# esp8266-dev2.net
KiCad netlist of a schematic drawn in EAGLE
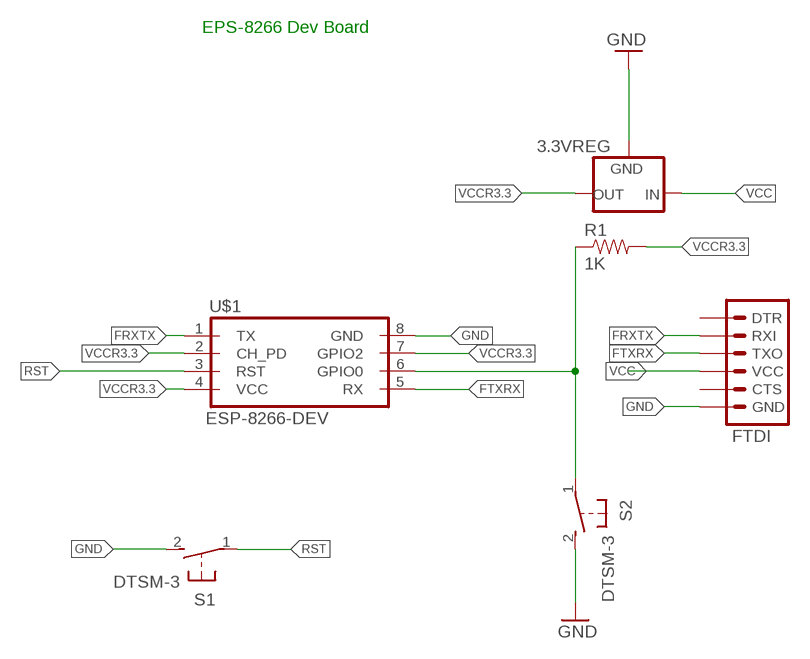
[diagram p0: schematic, sheet 1]

(export (version "E")
  (design (tool "Eeschema 10.0.6"))
  (components
    (comp (ref "3.3VREG")
      (value "LM1117V")
      (footprint "eagle-import:78XXS")
      (libsource (lib "eagle-import") (part "LM1117V"))
    )
    (comp (ref "FTDI")
      (value "ARDUINO_SERIAL_PROGRAMPTH")
      (footprint "eagle-import:1X06")
      (libsource (lib "eagle-import") (part "ARDUINO_SERIAL_PROGRAMPTH"))
    )
    (comp (ref "R1")
      (value "1K")
      (footprint "eagle-import:AXIAL-0.3EZ")
      (fields (field (name "MF") "FARNELL") (field (name "MPN") "MCF 0.25W 1K"))
      (libsource (lib "eagle-import") (part "1KOHM-1/4W-1%(PTH)HORIZ-KIT"))
    )
    (comp (ref "S1")
      (value "DTSM-3")
      (footprint "eagle-import:DTSM-3")
      (fields (field (name "MPN") "DTSM-32S-B"))
      (libsource (lib "eagle-import") (part "DTSM-3"))
    )
    (comp (ref "S2")
      (value "DTSM-3")
      (footprint "eagle-import:DTSM-3")
      (fields (field (name "MPN") "DTSM-32S-B"))
      (libsource (lib "eagle-import") (part "DTSM-3"))
    )
    (comp (ref "U$1")
      (value "ESP-8266-DEV")
      (footprint "eagle-import:2X4")
      (libsource (lib "eagle-import") (part "ESP-8266-DEV"))
    )
  )
  (nets
    (net (code "1") (name "FRXTX") (class "Default")
      (node (ref "FTDI") (pin "2") (pinfunction "RXI_2") (pintype "passive"))
      (node (ref "U$1") (pin "1") (pinfunction "TX_1") (pintype "bidirectional"))
    )
    (net (code "2") (name "FTXRX") (class "Default")
      (node (ref "FTDI") (pin "3") (pinfunction "TXO_3") (pintype "passive"))
      (node (ref "U$1") (pin "5") (pinfunction "RX_5") (pintype "bidirectional"))
    )
    (net (code "3") (name "GND") (class "Default")
      (node (ref "3.3VREG") (pin "GND") (pinfunction "GND_GND") (pintype "input"))
      (node (ref "FTDI") (pin "6") (pinfunction "GND_6") (pintype "passive"))
      (node (ref "S1") (pin "2") (pinfunction "2_2") (pintype "passive"))
      (node (ref "S2") (pin "2") (pinfunction "2_2") (pintype "passive"))
      (node (ref "U$1") (pin "8") (pinfunction "GND_8") (pintype "bidirectional"))
    )
    (net (code "4") (name "Net-(R1-1)") (class "Default")
      (node (ref "R1") (pin "P$1") (pinfunction "1_P$1") (pintype "passive"))
      (node (ref "S2") (pin "1") (pinfunction "1_1") (pintype "passive"))
      (node (ref "U$1") (pin "6") (pinfunction "GPIO0_6") (pintype "bidirectional"))
    )
    (net (code "5") (name "RST") (class "Default")
      (node (ref "S1") (pin "1") (pinfunction "1_1") (pintype "passive"))
      (node (ref "U$1") (pin "3") (pinfunction "RST_3") (pintype "bidirectional"))
    )
    (net (code "6") (name "VCC") (class "Default")
      (node (ref "3.3VREG") (pin "IN") (pinfunction "IN_IN") (pintype "input"))
      (node (ref "FTDI") (pin "4") (pinfunction "VCC_4") (pintype "passive"))
    )
    (net (code "7") (name "VCCR3.3") (class "Default")
      (node (ref "3.3VREG") (pin "OUT") (pinfunction "OUT_OUT") (pintype "passive"))
      (node (ref "R1") (pin "P$2") (pinfunction "2_P$2") (pintype "passive"))
      (node (ref "U$1") (pin "2") (pinfunction "CH_PD_2") (pintype "bidirectional"))
      (node (ref "U$1") (pin "4") (pinfunction "VCC_4") (pintype "bidirectional"))
      (node (ref "U$1") (pin "7") (pinfunction "GPIO2_7") (pintype "bidirectional"))
    )
    (net (code "8") (name "unconnected-(FTDI-CTS-Pad5)") (class "Default")
      (node (ref "FTDI") (pin "5") (pinfunction "CTS_5") (pintype "passive"))
    )
    (net (code "9") (name "unconnected-(FTDI-DTR-Pad1)") (class "Default")
      (node (ref "FTDI") (pin "1") (pinfunction "DTR_1") (pintype "passive"))
    )
  )
)
